# SAMA7G54_DDR3L.net
KiCad netlist of a schematic drawn in Altium Designer
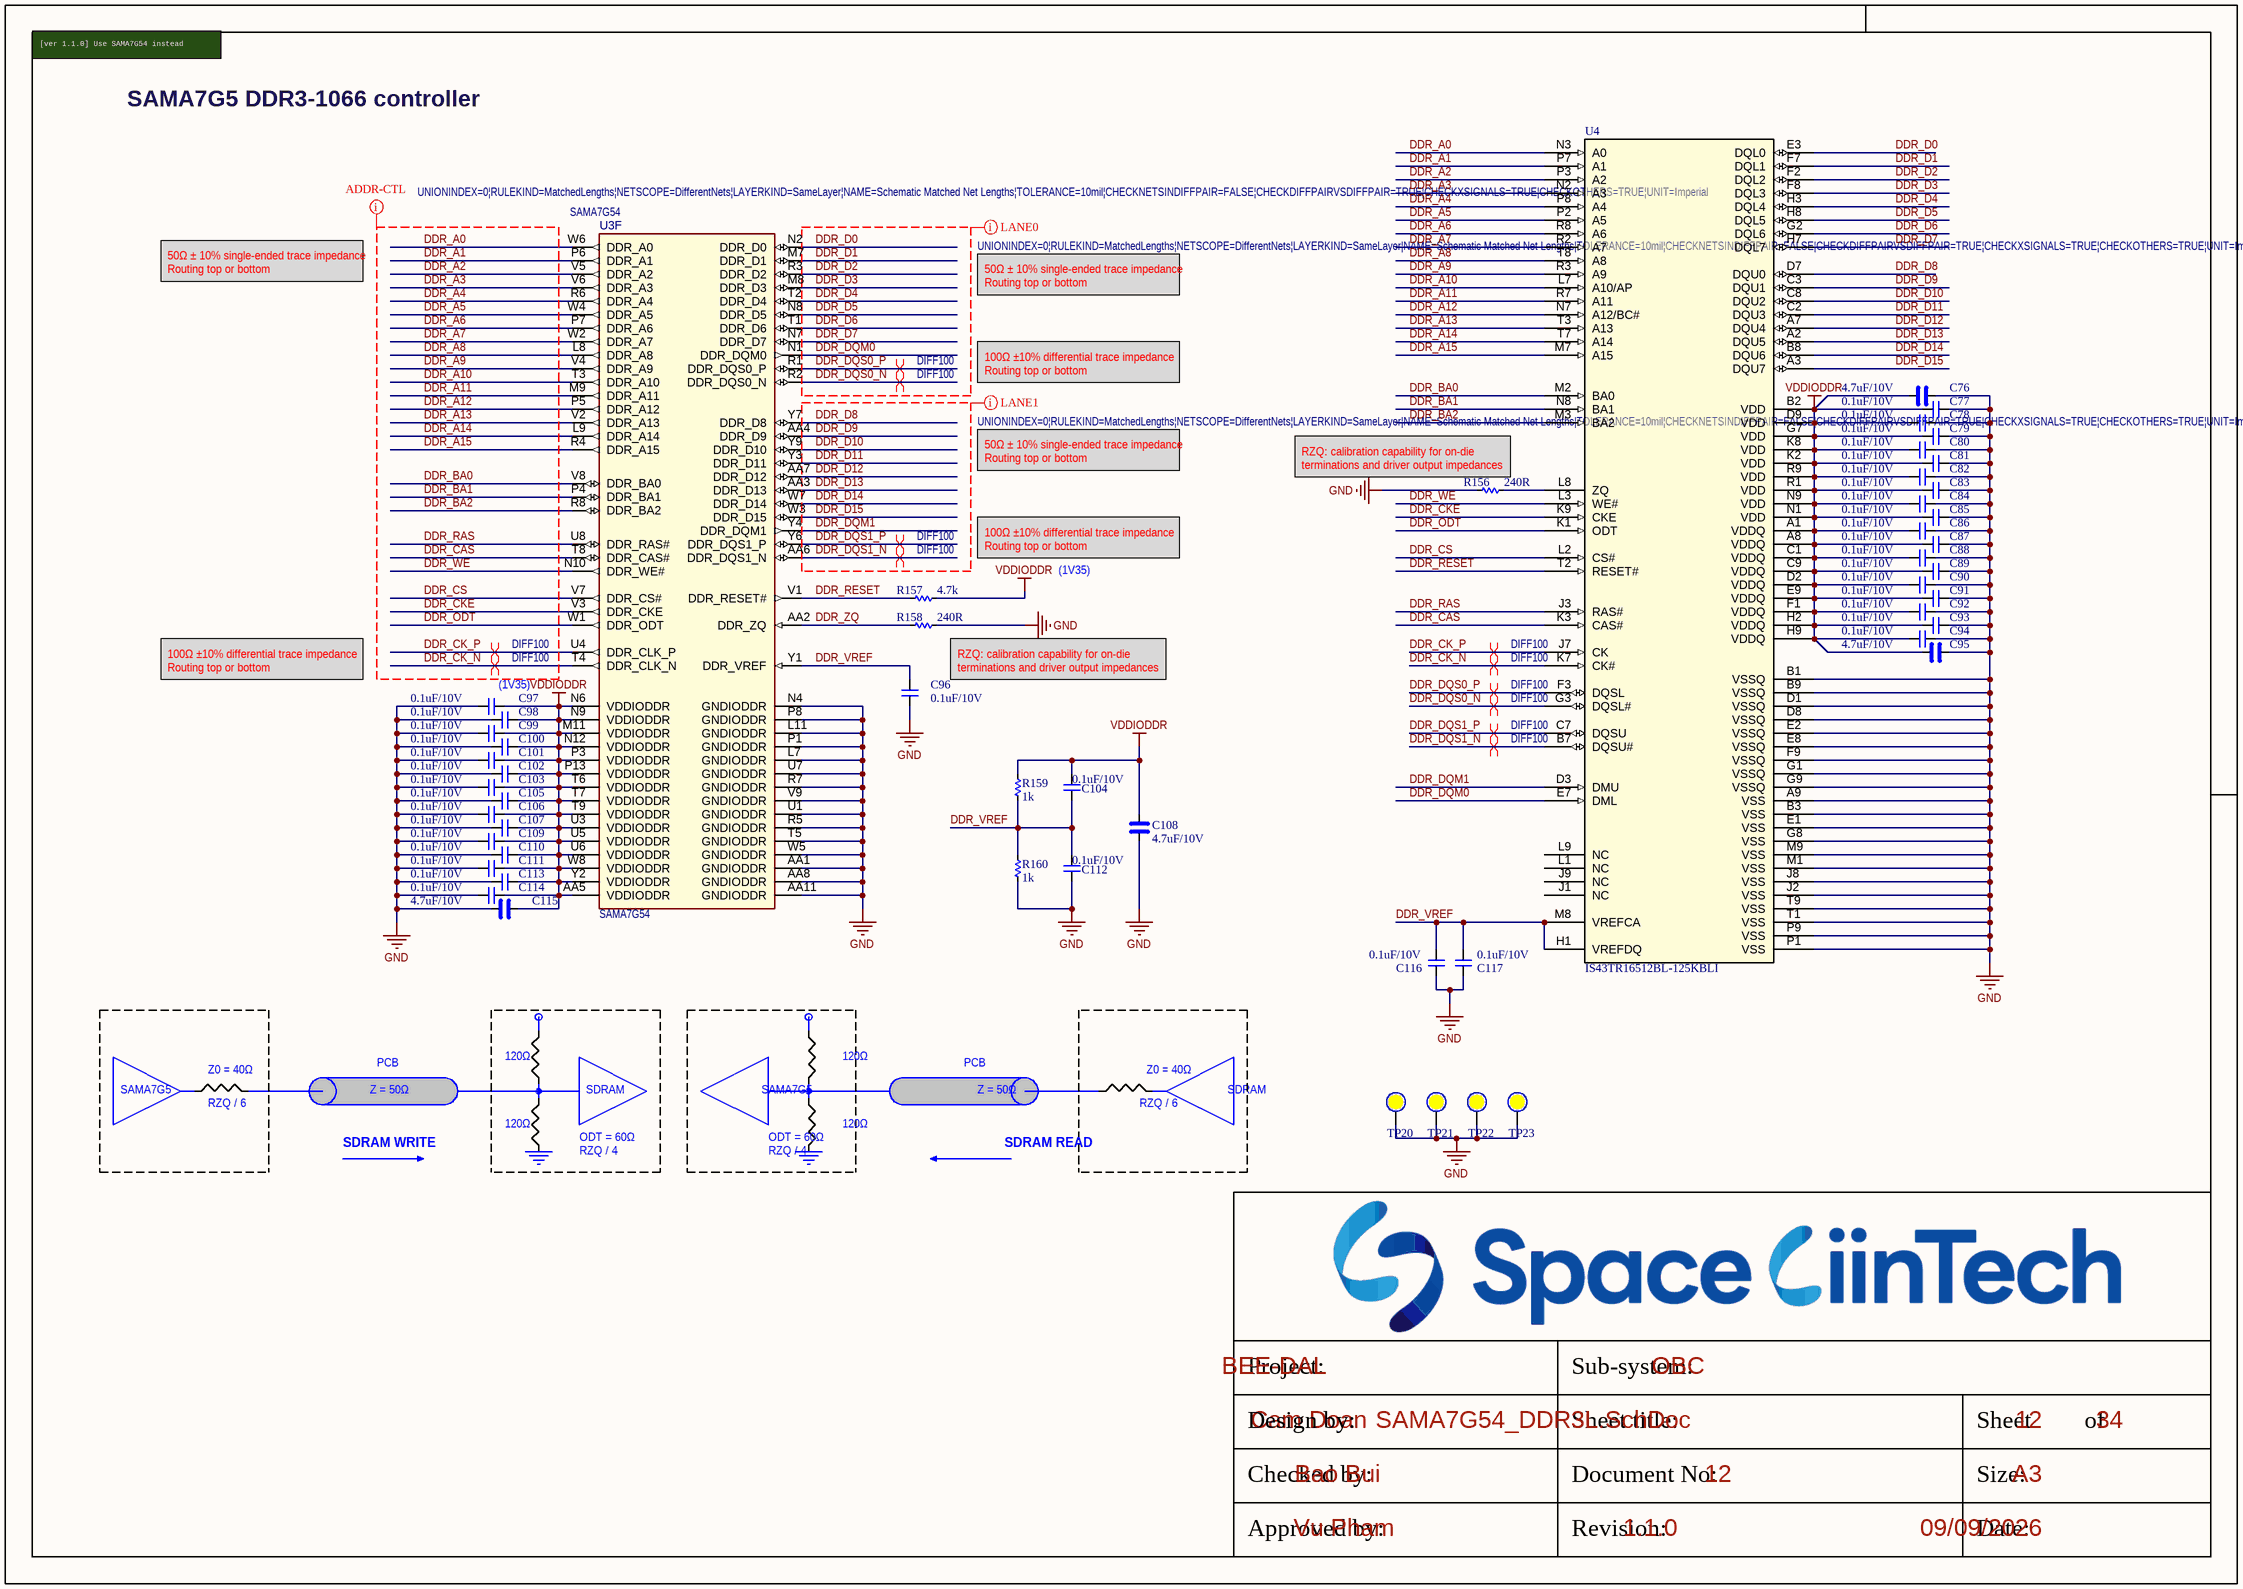
[diagram p0: SAMA7G54_DDR3L.SchDoc]

(export (version "E")
  (design (tool "Eeschema 10.0.6"))
  (components
    (comp (ref "C76")
      (value "4.7uF/10V")
      (footprint "CAP_C_1005X50_L")
      (description "CAP")
      (libsource (lib "LABLIB") (part "_CAP_C_High_2"))
    )
    (comp (ref "C77")
      (value "0.1uF/10V")
      (footprint "CAP_C_0603x30")
      (description "CAP")
      (libsource (lib "LABLIB") (part "_CAP_C_2"))
    )
    (comp (ref "C78")
      (value "0.1uF/10V")
      (footprint "CAP_C_0603x30")
      (description "CAP")
      (libsource (lib "LABLIB") (part "_CAP_C_2"))
    )
    (comp (ref "C79")
      (value "0.1uF/10V")
      (footprint "CAP_C_0603x30")
      (description "CAP")
      (libsource (lib "LABLIB") (part "_CAP_C_2"))
    )
    (comp (ref "C80")
      (value "0.1uF/10V")
      (footprint "CAP_C_0603x30")
      (description "CAP")
      (libsource (lib "LABLIB") (part "_CAP_C_2"))
    )
    (comp (ref "C81")
      (value "0.1uF/10V")
      (footprint "CAP_C_0603x30")
      (description "CAP")
      (libsource (lib "LABLIB") (part "_CAP_C_2"))
    )
    (comp (ref "C82")
      (value "0.1uF/10V")
      (footprint "CAP_C_0603x30")
      (description "CAP")
      (libsource (lib "LABLIB") (part "_CAP_C_2"))
    )
    (comp (ref "C83")
      (value "0.1uF/10V")
      (footprint "CAP_C_0603x30")
      (description "CAP")
      (libsource (lib "LABLIB") (part "_CAP_C_2"))
    )
    (comp (ref "C84")
      (value "0.1uF/10V")
      (footprint "CAP_C_0603x30")
      (description "CAP")
      (libsource (lib "LABLIB") (part "_CAP_C_2"))
    )
    (comp (ref "C85")
      (value "0.1uF/10V")
      (footprint "CAP_C_0603x30")
      (description "CAP")
      (libsource (lib "LABLIB") (part "_CAP_C_2"))
    )
    (comp (ref "C86")
      (value "0.1uF/10V")
      (footprint "CAP_C_0603x30")
      (description "CAP")
      (libsource (lib "LABLIB") (part "_CAP_C_2"))
    )
    (comp (ref "C87")
      (value "0.1uF/10V")
      (footprint "CAP_C_0603x30")
      (description "CAP")
      (libsource (lib "LABLIB") (part "_CAP_C_2"))
    )
    (comp (ref "C88")
      (value "0.1uF/10V")
      (footprint "CAP_C_0603x30")
      (description "CAP")
      (libsource (lib "LABLIB") (part "_CAP_C_2"))
    )
    (comp (ref "C89")
      (value "0.1uF/10V")
      (footprint "CAP_C_0603x30")
      (description "CAP")
      (libsource (lib "LABLIB") (part "_CAP_C_2"))
    )
    (comp (ref "C90")
      (value "0.1uF/10V")
      (footprint "CAP_C_0603x30")
      (description "CAP")
      (libsource (lib "LABLIB") (part "_CAP_C_2"))
    )
    (comp (ref "C91")
      (value "0.1uF/10V")
      (footprint "CAP_C_0603x30")
      (description "CAP")
      (libsource (lib "LABLIB") (part "_CAP_C_2"))
    )
    (comp (ref "C92")
      (value "0.1uF/10V")
      (footprint "CAP_C_0603x30")
      (description "CAP")
      (libsource (lib "LABLIB") (part "_CAP_C_2"))
    )
    (comp (ref "C93")
      (value "0.1uF/10V")
      (footprint "CAP_C_0603x30")
      (description "CAP")
      (libsource (lib "LABLIB") (part "_CAP_C_2"))
    )
    (comp (ref "C94")
      (value "0.1uF/10V")
      (footprint "CAP_C_0603x30")
      (description "CAP")
      (libsource (lib "LABLIB") (part "_CAP_C_2"))
    )
    (comp (ref "C95")
      (value "4.7uF/10V")
      (footprint "CAP_C_1005X50_L")
      (description "CAP")
      (libsource (lib "LABLIB") (part "_CAP_C_High_2"))
    )
    (comp (ref "C96")
      (value "0.1uF/10V")
      (footprint "CAP_C_0603x30")
      (description "CAP")
      (libsource (lib "LABLIB") (part "_CAP_C_2"))
    )
    (comp (ref "C97")
      (value "0.1uF/10V")
      (footprint "CAP_C_0603x30")
      (description "CAP")
      (libsource (lib "LABLIB") (part "_CAP_C_2"))
    )
    (comp (ref "C98")
      (value "0.1uF/10V")
      (footprint "CAP_C_0603x30")
      (description "CAP")
      (libsource (lib "LABLIB") (part "_CAP_C_2"))
    )
    (comp (ref "C99")
      (value "0.1uF/10V")
      (footprint "CAP_C_0603x30")
      (description "CAP")
      (libsource (lib "LABLIB") (part "_CAP_C_2"))
    )
    (comp (ref "C100")
      (value "0.1uF/10V")
      (footprint "CAP_C_0603x30")
      (description "CAP")
      (libsource (lib "LABLIB") (part "_CAP_C_2"))
    )
    (comp (ref "C101")
      (value "0.1uF/10V")
      (footprint "CAP_C_0603x30")
      (description "CAP")
      (libsource (lib "LABLIB") (part "_CAP_C_2"))
    )
    (comp (ref "C102")
      (value "0.1uF/10V")
      (footprint "CAP_C_0603x30")
      (description "CAP")
      (libsource (lib "LABLIB") (part "_CAP_C_2"))
    )
    (comp (ref "C103")
      (value "0.1uF/10V")
      (footprint "CAP_C_0603x30")
      (description "CAP")
      (libsource (lib "LABLIB") (part "_CAP_C_2"))
    )
    (comp (ref "C104")
      (value "0.1uF/10V")
      (footprint "CAP_C_0603x30")
      (description "CAP")
      (libsource (lib "LABLIB") (part "_CAP_C_2"))
    )
    (comp (ref "C105")
      (value "0.1uF/10V")
      (footprint "CAP_C_0603x30")
      (description "CAP")
      (libsource (lib "LABLIB") (part "_CAP_C_2"))
    )
    (comp (ref "C106")
      (value "0.1uF/10V")
      (footprint "CAP_C_0603x30")
      (description "CAP")
      (libsource (lib "LABLIB") (part "_CAP_C_2"))
    )
    (comp (ref "C107")
      (value "0.1uF/10V")
      (footprint "CAP_C_0603x30")
      (description "CAP")
      (libsource (lib "LABLIB") (part "_CAP_C_2"))
    )
    (comp (ref "C108")
      (value "4.7uF/10V")
      (footprint "CAP_C_1005X50_L")
      (description "CAP")
      (libsource (lib "LABLIB") (part "_CAP_C_High_2"))
    )
    (comp (ref "C109")
      (value "0.1uF/10V")
      (footprint "CAP_C_0603x30")
      (description "CAP")
      (libsource (lib "LABLIB") (part "_CAP_C_2"))
    )
    (comp (ref "C110")
      (value "0.1uF/10V")
      (footprint "CAP_C_0603x30")
      (description "CAP")
      (libsource (lib "LABLIB") (part "_CAP_C_2"))
    )
    (comp (ref "C111")
      (value "0.1uF/10V")
      (footprint "CAP_C_0603x30")
      (description "CAP")
      (libsource (lib "LABLIB") (part "_CAP_C_2"))
    )
    (comp (ref "C112")
      (value "0.1uF/10V")
      (footprint "CAP_C_0603x30")
      (description "CAP")
      (libsource (lib "LABLIB") (part "_CAP_C_2"))
    )
    (comp (ref "C113")
      (value "0.1uF/10V")
      (footprint "CAP_C_0603x30")
      (description "CAP")
      (libsource (lib "LABLIB") (part "_CAP_C_2"))
    )
    (comp (ref "C114")
      (value "0.1uF/10V")
      (footprint "CAP_C_0603x30")
      (description "CAP")
      (libsource (lib "LABLIB") (part "_CAP_C_2"))
    )
    (comp (ref "C115")
      (value "4.7uF/10V")
      (footprint "CAP_C_1005X50_L")
      (description "CAP")
      (libsource (lib "LABLIB") (part "_CAP_C_High_2"))
    )
    (comp (ref "C116")
      (value "0.1uF/10V")
      (footprint "CAP_C_0603x30")
      (description "CAP")
      (libsource (lib "LABLIB") (part "_CAP_C_2"))
    )
    (comp (ref "C117")
      (value "0.1uF/10V")
      (footprint "CAP_C_0603x30")
      (description "CAP")
      (libsource (lib "LABLIB") (part "_CAP_C_2"))
    )
    (comp (ref "R156")
      (value "240R")
      (footprint "RES_C_0603X30")
      (description "RES")
      (libsource (lib "LABLIB") (part "_RES_B_2"))
    )
    (comp (ref "R157")
      (value "4.7k")
      (footprint "RES_C_1005x30_L")
      (description "RES")
      (libsource (lib "LABLIB") (part "_RES_B_2"))
    )
    (comp (ref "R158")
      (value "240R")
      (footprint "RES_C_0603X30")
      (description "RES")
      (libsource (lib "LABLIB") (part "_RES_B_2"))
    )
    (comp (ref "R159")
      (value "1k")
      (footprint "RES_C_1005x30_L")
      (description "RES")
      (libsource (lib "LABLIB") (part "_RES_B_2"))
    )
    (comp (ref "R160")
      (value "1k")
      (footprint "RES_C_1005x30_L")
      (description "RES")
      (libsource (lib "LABLIB") (part "_RES_B_2"))
    )
    (comp (ref "TP20")
      (value "~")
      (footprint "Testpoint_80_pin0")
      (description "Test Point")
      (libsource (lib "IFBschelib") (part "Test Point"))
    )
    (comp (ref "TP21")
      (value "~")
      (footprint "Testpoint_80_pin0")
      (description "Test Point")
      (libsource (lib "IFBschelib") (part "Test Point"))
    )
    (comp (ref "TP22")
      (value "~")
      (footprint "Testpoint_80_pin0")
      (description "Test Point")
      (libsource (lib "IFBschelib") (part "Test Point"))
    )
    (comp (ref "TP23")
      (value "~")
      (footprint "Testpoint_80_pin0")
      (description "Test Point")
      (libsource (lib "IFBschelib") (part "Test Point"))
    )
    (comp (ref "U3")
      (value "SAMA7G54")
      (footprint "TFBGA-343_14x14 - 2.5mm")
      (description "SAMA7G54 MPU 1000MHz Cortex-A7 TFBGA-343")
      (fields (field (name "ALTIUM_VALUE") "SAMA7G54") (field (name "OWNER") "Ciprian Abramov"))
      (libsource (lib "LABLIB") (part "SAMA7G54"))
    )
    (comp (ref "U4")
      (value "IS43TR16512BL-125KBLI")
      (footprint "TWBGA96_ISI")
      (description "DDR3L")
      (fields (field (name "COPYRIGHT") "Copyright (C) 2025 Ultra Librarian. All rights reserved."))
      (libsource (lib "LABLIB") (part "IC_RAM_IS43TR16512BL-125KBLI"))
    )
  )
  (nets
    (net (code "1") (name "/DDR_A0") (class "Default")
      (node (ref "U3") (pin "W6") (pinfunction "DDR_A0_W6") (pintype "output"))
      (node (ref "U4") (pin "N3") (pinfunction "A0_N3") (pintype "input"))
    )
    (net (code "2") (name "/DDR_A1") (class "Default")
      (node (ref "U3") (pin "P6") (pinfunction "DDR_A1_P6") (pintype "output"))
      (node (ref "U4") (pin "P7") (pinfunction "A1_P7") (pintype "input"))
    )
    (net (code "3") (name "/DDR_A2") (class "Default")
      (node (ref "U3") (pin "V5") (pinfunction "DDR_A2_V5") (pintype "output"))
      (node (ref "U4") (pin "P3") (pinfunction "A2_P3") (pintype "input"))
    )
    (net (code "4") (name "/DDR_A3") (class "Default")
      (node (ref "U3") (pin "V6") (pinfunction "DDR_A3_V6") (pintype "output"))
      (node (ref "U4") (pin "N2") (pinfunction "A3_N2") (pintype "input"))
    )
    (net (code "5") (name "/DDR_A4") (class "Default")
      (node (ref "U3") (pin "R6") (pinfunction "DDR_A4_R6") (pintype "output"))
      (node (ref "U4") (pin "P8") (pinfunction "A4_P8") (pintype "input"))
    )
    (net (code "6") (name "/DDR_A5") (class "Default")
      (node (ref "U3") (pin "W4") (pinfunction "DDR_A5_W4") (pintype "output"))
      (node (ref "U4") (pin "P2") (pinfunction "A5_P2") (pintype "input"))
    )
    (net (code "7") (name "/DDR_A6") (class "Default")
      (node (ref "U3") (pin "P7") (pinfunction "DDR_A6_P7") (pintype "output"))
      (node (ref "U4") (pin "R8") (pinfunction "A6_R8") (pintype "input"))
    )
    (net (code "8") (name "/DDR_A7") (class "Default")
      (node (ref "U3") (pin "W2") (pinfunction "DDR_A7_W2") (pintype "output"))
      (node (ref "U4") (pin "R2") (pinfunction "A7_R2") (pintype "input"))
    )
    (net (code "9") (name "/DDR_A8") (class "Default")
      (node (ref "U3") (pin "L8") (pinfunction "DDR_A8_L8") (pintype "output"))
      (node (ref "U4") (pin "T8") (pinfunction "A8_T8") (pintype "input"))
    )
    (net (code "10") (name "/DDR_A9") (class "Default")
      (node (ref "U3") (pin "V4") (pinfunction "DDR_A9_V4") (pintype "output"))
      (node (ref "U4") (pin "R3") (pinfunction "A9_R3") (pintype "input"))
    )
    (net (code "11") (name "/DDR_A10") (class "Default")
      (node (ref "U3") (pin "T3") (pinfunction "DDR_A10_T3") (pintype "output"))
      (node (ref "U4") (pin "L7") (pinfunction "A10/AP_L7") (pintype "input"))
    )
    (net (code "12") (name "/DDR_A11") (class "Default")
      (node (ref "U3") (pin "M9") (pinfunction "DDR_A11_M9") (pintype "output"))
      (node (ref "U4") (pin "R7") (pinfunction "A11_R7") (pintype "input"))
    )
    (net (code "13") (name "/DDR_A12") (class "Default")
      (node (ref "U3") (pin "P5") (pinfunction "DDR_A12_P5") (pintype "output"))
      (node (ref "U4") (pin "N7") (pinfunction "A12/BC#_N7") (pintype "input"))
    )
    (net (code "14") (name "/DDR_A13") (class "Default")
      (node (ref "U3") (pin "V2") (pinfunction "DDR_A13_V2") (pintype "output"))
      (node (ref "U4") (pin "T3") (pinfunction "A13_T3") (pintype "input"))
    )
    (net (code "15") (name "/DDR_A14") (class "Default")
      (node (ref "U3") (pin "L9") (pinfunction "DDR_A14_L9") (pintype "output"))
      (node (ref "U4") (pin "T7") (pinfunction "A14_T7") (pintype "input"))
    )
    (net (code "16") (name "/DDR_A15") (class "Default")
      (node (ref "U3") (pin "R4") (pinfunction "DDR_A15_R4") (pintype "output"))
      (node (ref "U4") (pin "M7") (pinfunction "A15_M7") (pintype "input"))
    )
    (net (code "17") (name "/DDR_BA0") (class "Default")
      (node (ref "U3") (pin "V8") (pinfunction "DDR_BA0_V8") (pintype "bidirectional"))
      (node (ref "U4") (pin "M2") (pinfunction "BA0_M2") (pintype "input"))
    )
    (net (code "18") (name "/DDR_BA1") (class "Default")
      (node (ref "U3") (pin "P4") (pinfunction "DDR_BA1_P4") (pintype "bidirectional"))
      (node (ref "U4") (pin "N8") (pinfunction "BA1_N8") (pintype "input"))
    )
    (net (code "19") (name "/DDR_BA2") (class "Default")
      (node (ref "U3") (pin "R8") (pinfunction "DDR_BA2_R8") (pintype "bidirectional"))
      (node (ref "U4") (pin "M3") (pinfunction "BA2_M3") (pintype "input"))
    )
    (net (code "20") (name "/DDR_CAS") (class "Default")
      (node (ref "U3") (pin "T8") (pinfunction "DDR_CAS#_T8") (pintype "bidirectional"))
      (node (ref "U4") (pin "K3") (pinfunction "CAS#_K3") (pintype "input"))
    )
    (net (code "21") (name "/DDR_CKE") (class "Default")
      (node (ref "U3") (pin "V3") (pinfunction "DDR_CKE_V3") (pintype "output"))
      (node (ref "U4") (pin "K9") (pinfunction "CKE_K9") (pintype "input"))
    )
    (net (code "22") (name "/DDR_CK_N") (class "Default")
      (node (ref "U3") (pin "T4") (pinfunction "DDR_CLK_N_T4") (pintype "output"))
      (node (ref "U4") (pin "K7") (pinfunction "CK#_K7") (pintype "input"))
    )
    (net (code "23") (name "/DDR_CK_P") (class "Default")
      (node (ref "U3") (pin "U4") (pinfunction "DDR_CLK_P_U4") (pintype "output"))
      (node (ref "U4") (pin "J7") (pinfunction "CK_J7") (pintype "input"))
    )
    (net (code "24") (name "/DDR_CS") (class "Default")
      (node (ref "U3") (pin "V7") (pinfunction "DDR_CS#_V7") (pintype "output"))
      (node (ref "U4") (pin "L2") (pinfunction "CS#_L2") (pintype "input"))
    )
    (net (code "25") (name "/DDR_D0") (class "Default")
      (node (ref "U3") (pin "N2") (pinfunction "DDR_D0_N2") (pintype "bidirectional"))
      (node (ref "U4") (pin "E3") (pinfunction "DQL0_E3") (pintype "bidirectional"))
    )
    (net (code "26") (name "/DDR_D1") (class "Default")
      (node (ref "U3") (pin "M7") (pinfunction "DDR_D1_M7") (pintype "bidirectional"))
      (node (ref "U4") (pin "F7") (pinfunction "DQL1_F7") (pintype "bidirectional"))
    )
    (net (code "27") (name "/DDR_D2") (class "Default")
      (node (ref "U3") (pin "R3") (pinfunction "DDR_D2_R3") (pintype "bidirectional"))
      (node (ref "U4") (pin "F2") (pinfunction "DQL2_F2") (pintype "bidirectional"))
    )
    (net (code "28") (name "/DDR_D3") (class "Default")
      (node (ref "U3") (pin "M8") (pinfunction "DDR_D3_M8") (pintype "bidirectional"))
      (node (ref "U4") (pin "F8") (pinfunction "DQL3_F8") (pintype "bidirectional"))
    )
    (net (code "29") (name "/DDR_D4") (class "Default")
      (node (ref "U3") (pin "T2") (pinfunction "DDR_D4_T2") (pintype "bidirectional"))
      (node (ref "U4") (pin "H3") (pinfunction "DQL4_H3") (pintype "bidirectional"))
    )
    (net (code "30") (name "/DDR_D5") (class "Default")
      (node (ref "U3") (pin "N8") (pinfunction "DDR_D5_N8") (pintype "bidirectional"))
      (node (ref "U4") (pin "H8") (pinfunction "DQL5_H8") (pintype "bidirectional"))
    )
    (net (code "31") (name "/DDR_D6") (class "Default")
      (node (ref "U3") (pin "T1") (pinfunction "DDR_D6_T1") (pintype "bidirectional"))
      (node (ref "U4") (pin "G2") (pinfunction "DQL6_G2") (pintype "bidirectional"))
    )
    (net (code "32") (name "/DDR_D7") (class "Default")
      (node (ref "U3") (pin "N7") (pinfunction "DDR_D7_N7") (pintype "bidirectional"))
      (node (ref "U4") (pin "H7") (pinfunction "DQL7_H7") (pintype "bidirectional"))
    )
    (net (code "33") (name "/DDR_D8") (class "Default")
      (node (ref "U3") (pin "Y7") (pinfunction "DDR_D8_Y7") (pintype "bidirectional"))
      (node (ref "U4") (pin "D7") (pinfunction "DQU0_D7") (pintype "bidirectional"))
    )
    (net (code "34") (name "/DDR_D9") (class "Default")
      (node (ref "U3") (pin "AA4") (pinfunction "DDR_D9_AA4") (pintype "bidirectional"))
      (node (ref "U4") (pin "C3") (pinfunction "DQU1_C3") (pintype "bidirectional"))
    )
    (net (code "35") (name "/DDR_D10") (class "Default")
      (node (ref "U3") (pin "Y9") (pinfunction "DDR_D10_Y9") (pintype "bidirectional"))
      (node (ref "U4") (pin "C8") (pinfunction "DQU2_C8") (pintype "bidirectional"))
    )
    (net (code "36") (name "/DDR_D11") (class "Default")
      (node (ref "U3") (pin "Y3") (pinfunction "DDR_D11_Y3") (pintype "bidirectional"))
      (node (ref "U4") (pin "C2") (pinfunction "DQU3_C2") (pintype "bidirectional"))
    )
    (net (code "37") (name "/DDR_D12") (class "Default")
      (node (ref "U3") (pin "AA7") (pinfunction "DDR_D12_AA7") (pintype "bidirectional"))
      (node (ref "U4") (pin "A7") (pinfunction "DQU4_A7") (pintype "bidirectional"))
    )
    (net (code "38") (name "/DDR_D13") (class "Default")
      (node (ref "U3") (pin "AA3") (pinfunction "DDR_D13_AA3") (pintype "bidirectional"))
      (node (ref "U4") (pin "A2") (pinfunction "DQU5_A2") (pintype "bidirectional"))
    )
    (net (code "39") (name "/DDR_D14") (class "Default")
      (node (ref "U3") (pin "W7") (pinfunction "DDR_D14_W7") (pintype "bidirectional"))
      (node (ref "U4") (pin "B8") (pinfunction "DQU6_B8") (pintype "bidirectional"))
    )
    (net (code "40") (name "/DDR_D15") (class "Default")
      (node (ref "U3") (pin "W3") (pinfunction "DDR_D15_W3") (pintype "bidirectional"))
      (node (ref "U4") (pin "A3") (pinfunction "DQU7_A3") (pintype "bidirectional"))
    )
    (net (code "41") (name "/DDR_DQM0") (class "Default")
      (node (ref "U3") (pin "N1") (pinfunction "DDR_DQM0_N1") (pintype "output"))
      (node (ref "U4") (pin "E7") (pinfunction "DML_E7") (pintype "input"))
    )
    (net (code "42") (name "/DDR_DQM1") (class "Default")
      (node (ref "U3") (pin "Y4") (pinfunction "DDR_DQM1_Y4") (pintype "output"))
      (node (ref "U4") (pin "D3") (pinfunction "DMU_D3") (pintype "input"))
    )
    (net (code "43") (name "/DDR_DQS0_N") (class "Default")
      (node (ref "U3") (pin "R2") (pinfunction "DDR_DQS0_N_R2") (pintype "bidirectional"))
      (node (ref "U4") (pin "G3") (pinfunction "DQSL#_G3") (pintype "bidirectional"))
    )
    (net (code "44") (name "/DDR_DQS0_P") (class "Default")
      (node (ref "U3") (pin "R1") (pinfunction "DDR_DQS0_P_R1") (pintype "bidirectional"))
      (node (ref "U4") (pin "F3") (pinfunction "DQSL_F3") (pintype "bidirectional"))
    )
    (net (code "45") (name "/DDR_DQS1_N") (class "Default")
      (node (ref "U3") (pin "AA6") (pinfunction "DDR_DQS1_N_AA6") (pintype "bidirectional"))
      (node (ref "U4") (pin "B7") (pinfunction "DQSU#_B7") (pintype "bidirectional"))
    )
    (net (code "46") (name "/DDR_DQS1_P") (class "Default")
      (node (ref "U3") (pin "Y6") (pinfunction "DDR_DQS1_P_Y6") (pintype "bidirectional"))
      (node (ref "U4") (pin "C7") (pinfunction "DQSU_C7") (pintype "bidirectional"))
    )
    (net (code "47") (name "/DDR_ODT") (class "Default")
      (node (ref "U3") (pin "W1") (pinfunction "DDR_ODT_W1") (pintype "output"))
      (node (ref "U4") (pin "K1") (pinfunction "ODT_K1") (pintype "input"))
    )
    (net (code "48") (name "/DDR_RAS") (class "Default")
      (node (ref "U3") (pin "U8") (pinfunction "DDR_RAS#_U8") (pintype "bidirectional"))
      (node (ref "U4") (pin "J3") (pinfunction "RAS#_J3") (pintype "input"))
    )
    (net (code "49") (name "/DDR_RESET") (class "Default")
      (node (ref "R157") (pin "2") (pinfunction "2_2") (pintype "passive"))
      (node (ref "U3") (pin "V1") (pinfunction "DDR_RESET#_V1") (pintype "output"))
      (node (ref "U4") (pin "T2") (pinfunction "RESET#_T2") (pintype "input"))
    )
    (net (code "50") (name "/DDR_VREF") (class "Default")
      (node (ref "C104") (pin "2") (pinfunction "2_2") (pintype "passive"))
      (node (ref "C112") (pin "1") (pinfunction "1_1") (pintype "passive"))
      (node (ref "C116") (pin "1") (pinfunction "1_1") (pintype "passive"))
      (node (ref "C117") (pin "1") (pinfunction "1_1") (pintype "passive"))
      (node (ref "C96") (pin "1") (pinfunction "1_1") (pintype "passive"))
      (node (ref "R159") (pin "2") (pinfunction "2_2") (pintype "passive"))
      (node (ref "R160") (pin "1") (pinfunction "1_1") (pintype "passive"))
      (node (ref "U3") (pin "Y1") (pinfunction "DDR_VREF_Y1") (pintype "input"))
      (node (ref "U4") (pin "H1") (pinfunction "VREFDQ_H1") (pintype "power_in"))
      (node (ref "U4") (pin "M8") (pinfunction "VREFCA_M8") (pintype "power_in"))
    )
    (net (code "51") (name "/DDR_WE") (class "Default")
      (node (ref "U3") (pin "N10") (pinfunction "DDR_WE#_N10") (pintype "output"))
      (node (ref "U4") (pin "L3") (pinfunction "WE#_L3") (pintype "input"))
    )
    (net (code "52") (name "/DDR_ZQ") (class "Default")
      (node (ref "R158") (pin "2") (pinfunction "2_2") (pintype "passive"))
      (node (ref "U3") (pin "AA2") (pinfunction "DDR_ZQ_AA2") (pintype "input"))
    )
    (net (code "53") (name "GND") (class "Default")
      (node (ref "C100") (pin "2") (pinfunction "2_2") (pintype "passive"))
      (node (ref "C101") (pin "2") (pinfunction "2_2") (pintype "passive"))
      (node (ref "C102") (pin "2") (pinfunction "2_2") (pintype "passive"))
      (node (ref "C103") (pin "2") (pinfunction "2_2") (pintype "passive"))
      (node (ref "C105") (pin "2") (pinfunction "2_2") (pintype "passive"))
      (node (ref "C106") (pin "2") (pinfunction "2_2") (pintype "passive"))
      (node (ref "C107") (pin "2") (pinfunction "2_2") (pintype "passive"))
      (node (ref "C108") (pin "2") (pinfunction "2_2") (pintype "passive"))
      (node (ref "C109") (pin "2") (pinfunction "2_2") (pintype "passive"))
      (node (ref "C110") (pin "2") (pinfunction "2_2") (pintype "passive"))
      (node (ref "C111") (pin "2") (pinfunction "2_2") (pintype "passive"))
      (node (ref "C112") (pin "2") (pinfunction "2_2") (pintype "passive"))
      (node (ref "C113") (pin "2") (pinfunction "2_2") (pintype "passive"))
      (node (ref "C114") (pin "2") (pinfunction "2_2") (pintype "passive"))
      (node (ref "C115") (pin "2") (pinfunction "2_2") (pintype "passive"))
      (node (ref "C116") (pin "2") (pinfunction "2_2") (pintype "passive"))
      (node (ref "C117") (pin "2") (pinfunction "2_2") (pintype "passive"))
      (node (ref "C76") (pin "1") (pinfunction "1_1") (pintype "passive"))
      (node (ref "C77") (pin "1") (pinfunction "1_1") (pintype "passive"))
      (node (ref "C78") (pin "1") (pinfunction "1_1") (pintype "passive"))
      (node (ref "C79") (pin "1") (pinfunction "1_1") (pintype "passive"))
      (node (ref "C80") (pin "1") (pinfunction "1_1") (pintype "passive"))
      (node (ref "C81") (pin "1") (pinfunction "1_1") (pintype "passive"))
      (node (ref "C82") (pin "1") (pinfunction "1_1") (pintype "passive"))
      (node (ref "C83") (pin "1") (pinfunction "1_1") (pintype "passive"))
      (node (ref "C84") (pin "1") (pinfunction "1_1") (pintype "passive"))
      (node (ref "C85") (pin "1") (pinfunction "1_1") (pintype "passive"))
      (node (ref "C86") (pin "1") (pinfunction "1_1") (pintype "passive"))
      (node (ref "C87") (pin "1") (pinfunction "1_1") (pintype "passive"))
      (node (ref "C88") (pin "1") (pinfunction "1_1") (pintype "passive"))
      (node (ref "C89") (pin "1") (pinfunction "1_1") (pintype "passive"))
      (node (ref "C90") (pin "1") (pinfunction "1_1") (pintype "passive"))
      (node (ref "C91") (pin "1") (pinfunction "1_1") (pintype "passive"))
      (node (ref "C92") (pin "1") (pinfunction "1_1") (pintype "passive"))
      (node (ref "C93") (pin "1") (pinfunction "1_1") (pintype "passive"))
      (node (ref "C94") (pin "1") (pinfunction "1_1") (pintype "passive"))
      (node (ref "C95") (pin "1") (pinfunction "1_1") (pintype "passive"))
      (node (ref "C96") (pin "2") (pinfunction "2_2") (pintype "passive"))
      (node (ref "C97") (pin "2") (pinfunction "2_2") (pintype "passive"))
      (node (ref "C98") (pin "2") (pinfunction "2_2") (pintype "passive"))
      (node (ref "C99") (pin "2") (pinfunction "2_2") (pintype "passive"))
      (node (ref "R156") (pin "2") (pinfunction "2_2") (pintype "passive"))
      (node (ref "R158") (pin "1") (pinfunction "1_1") (pintype "passive"))
      (node (ref "R160") (pin "2") (pinfunction "2_2") (pintype "passive"))
      (node (ref "TP20") (pin "0") (pinfunction "0_0") (pintype "passive"))
      (node (ref "TP21") (pin "0") (pinfunction "0_0") (pintype "passive"))
      (node (ref "TP22") (pin "0") (pinfunction "0_0") (pintype "passive"))
      (node (ref "TP23") (pin "0") (pinfunction "0_0") (pintype "passive"))
      (node (ref "U3") (pin "AA1") (pinfunction "GNDIODDR_AA1") (pintype "power_in"))
      (node (ref "U3") (pin "AA11") (pinfunction "GNDIODDR_AA11") (pintype "power_in"))
      (node (ref "U3") (pin "AA8") (pinfunction "GNDIODDR_AA8") (pintype "power_in"))
      (node (ref "U3") (pin "L11") (pinfunction "GNDIODDR_L11") (pintype "power_in"))
      (node (ref "U3") (pin "L7") (pinfunction "GNDIODDR_L7") (pintype "power_in"))
      (node (ref "U3") (pin "N4") (pinfunction "GNDIODDR_N4") (pintype "power_in"))
      (node (ref "U3") (pin "P1") (pinfunction "GNDIODDR_P1") (pintype "power_in"))
      (node (ref "U3") (pin "P8") (pinfunction "GNDIODDR_P8") (pintype "power_in"))
      (node (ref "U3") (pin "R5") (pinfunction "GNDIODDR_R5") (pintype "power_in"))
      (node (ref "U3") (pin "R7") (pinfunction "GNDIODDR_R7") (pintype "power_in"))
      (node (ref "U3") (pin "T5") (pinfunction "GNDIODDR_T5") (pintype "power_in"))
      (node (ref "U3") (pin "U1") (pinfunction "GNDIODDR_U1") (pintype "power_in"))
      (node (ref "U3") (pin "U7") (pinfunction "GNDIODDR_U7") (pintype "power_in"))
      (node (ref "U3") (pin "V9") (pinfunction "GNDIODDR_V9") (pintype "power_in"))
      (node (ref "U3") (pin "W5") (pinfunction "GNDIODDR_W5") (pintype "power_in"))
      (node (ref "U4") (pin "A9") (pinfunction "VSS_A9") (pintype "power_in"))
      (node (ref "U4") (pin "B1") (pinfunction "VSSQ_B1") (pintype "power_in"))
      (node (ref "U4") (pin "B3") (pinfunction "VSS_B3") (pintype "power_in"))
      (node (ref "U4") (pin "B9") (pinfunction "VSSQ_B9") (pintype "power_in"))
      (node (ref "U4") (pin "D1") (pinfunction "VSSQ_D1") (pintype "power_in"))
      (node (ref "U4") (pin "D8") (pinfunction "VSSQ_D8") (pintype "power_in"))
      (node (ref "U4") (pin "E1") (pinfunction "VSS_E1") (pintype "power_in"))
      (node (ref "U4") (pin "E2") (pinfunction "VSSQ_E2") (pintype "power_in"))
      (node (ref "U4") (pin "E8") (pinfunction "VSSQ_E8") (pintype "power_in"))
      (node (ref "U4") (pin "F9") (pinfunction "VSSQ_F9") (pintype "power_in"))
      (node (ref "U4") (pin "G1") (pinfunction "VSSQ_G1") (pintype "power_in"))
      (node (ref "U4") (pin "G8") (pinfunction "VSS_G8") (pintype "power_in"))
      (node (ref "U4") (pin "G9") (pinfunction "VSSQ_G9") (pintype "power_in"))
      (node (ref "U4") (pin "J2") (pinfunction "VSS_J2") (pintype "power_in"))
      (node (ref "U4") (pin "J8") (pinfunction "VSS_J8") (pintype "power_in"))
      (node (ref "U4") (pin "M1") (pinfunction "VSS_M1") (pintype "power_in"))
      (node (ref "U4") (pin "M9") (pinfunction "VSS_M9") (pintype "power_in"))
      (node (ref "U4") (pin "P1") (pinfunction "VSS_P1") (pintype "power_in"))
      (node (ref "U4") (pin "P9") (pinfunction "VSS_P9") (pintype "power_in"))
      (node (ref "U4") (pin "T1") (pinfunction "VSS_T1") (pintype "power_in"))
      (node (ref "U4") (pin "T9") (pinfunction "VSS_T9") (pintype "power_in"))
    )
    (net (code "54") (name "Net-(U4-ZQ)") (class "Default")
      (node (ref "R156") (pin "1") (pinfunction "1_1") (pintype "passive"))
      (node (ref "U4") (pin "L8") (pinfunction "ZQ_L8") (pintype "power_in"))
    )
    (net (code "55") (name "VDDIODDR") (class "Default")
      (node (ref "C100") (pin "1") (pinfunction "1_1") (pintype "passive"))
      (node (ref "C101") (pin "1") (pinfunction "1_1") (pintype "passive"))
      (node (ref "C102") (pin "1") (pinfunction "1_1") (pintype "passive"))
      (node (ref "C103") (pin "1") (pinfunction "1_1") (pintype "passive"))
      (node (ref "C104") (pin "1") (pinfunction "1_1") (pintype "passive"))
      (node (ref "C105") (pin "1") (pinfunction "1_1") (pintype "passive"))
      (node (ref "C106") (pin "1") (pinfunction "1_1") (pintype "passive"))
      (node (ref "C107") (pin "1") (pinfunction "1_1") (pintype "passive"))
      (node (ref "C108") (pin "1") (pinfunction "1_1") (pintype "passive"))
      (node (ref "C109") (pin "1") (pinfunction "1_1") (pintype "passive"))
      (node (ref "C110") (pin "1") (pinfunction "1_1") (pintype "passive"))
      (node (ref "C111") (pin "1") (pinfunction "1_1") (pintype "passive"))
      (node (ref "C113") (pin "1") (pinfunction "1_1") (pintype "passive"))
      (node (ref "C114") (pin "1") (pinfunction "1_1") (pintype "passive"))
      (node (ref "C115") (pin "1") (pinfunction "1_1") (pintype "passive"))
      (node (ref "C76") (pin "2") (pinfunction "2_2") (pintype "passive"))
      (node (ref "C77") (pin "2") (pinfunction "2_2") (pintype "passive"))
      (node (ref "C78") (pin "2") (pinfunction "2_2") (pintype "passive"))
      (node (ref "C79") (pin "2") (pinfunction "2_2") (pintype "passive"))
      (node (ref "C80") (pin "2") (pinfunction "2_2") (pintype "passive"))
      (node (ref "C81") (pin "2") (pinfunction "2_2") (pintype "passive"))
      (node (ref "C82") (pin "2") (pinfunction "2_2") (pintype "passive"))
      (node (ref "C83") (pin "2") (pinfunction "2_2") (pintype "passive"))
      (node (ref "C84") (pin "2") (pinfunction "2_2") (pintype "passive"))
      (node (ref "C85") (pin "2") (pinfunction "2_2") (pintype "passive"))
      (node (ref "C86") (pin "2") (pinfunction "2_2") (pintype "passive"))
      (node (ref "C87") (pin "2") (pinfunction "2_2") (pintype "passive"))
      (node (ref "C88") (pin "2") (pinfunction "2_2") (pintype "passive"))
      (node (ref "C89") (pin "2") (pinfunction "2_2") (pintype "passive"))
      (node (ref "C90") (pin "2") (pinfunction "2_2") (pintype "passive"))
      (node (ref "C91") (pin "2") (pinfunction "2_2") (pintype "passive"))
      (node (ref "C92") (pin "2") (pinfunction "2_2") (pintype "passive"))
      (node (ref "C93") (pin "2") (pinfunction "2_2") (pintype "passive"))
      (node (ref "C94") (pin "2") (pinfunction "2_2") (pintype "passive"))
      (node (ref "C95") (pin "2") (pinfunction "2_2") (pintype "passive"))
      (node (ref "C97") (pin "1") (pinfunction "1_1") (pintype "passive"))
      (node (ref "C98") (pin "1") (pinfunction "1_1") (pintype "passive"))
      (node (ref "C99") (pin "1") (pinfunction "1_1") (pintype "passive"))
      (node (ref "R157") (pin "1") (pinfunction "1_1") (pintype "passive"))
      (node (ref "R159") (pin "1") (pinfunction "1_1") (pintype "passive"))
      (node (ref "U3") (pin "AA5") (pinfunction "VDDIODDR_AA5") (pintype "power_in"))
      (node (ref "U3") (pin "M11") (pinfunction "VDDIODDR_M11") (pintype "power_in"))
      (node (ref "U3") (pin "N12") (pinfunction "VDDIODDR_N12") (pintype "power_in"))
      (node (ref "U3") (pin "N6") (pinfunction "VDDIODDR_N6") (pintype "power_in"))
      (node (ref "U3") (pin "N9") (pinfunction "VDDIODDR_N9") (pintype "power_in"))
      (node (ref "U3") (pin "P13") (pinfunction "VDDIODDR_P13") (pintype "power_in"))
      (node (ref "U3") (pin "P3") (pinfunction "VDDIODDR_P3") (pintype "power_in"))
      (node (ref "U3") (pin "T6") (pinfunction "VDDIODDR_T6") (pintype "power_in"))
      (node (ref "U3") (pin "T7") (pinfunction "VDDIODDR_T7") (pintype "power_in"))
      (node (ref "U3") (pin "T9") (pinfunction "VDDIODDR_T9") (pintype "power_in"))
      (node (ref "U3") (pin "U3") (pinfunction "VDDIODDR_U3") (pintype "power_in"))
      (node (ref "U3") (pin "U5") (pinfunction "VDDIODDR_U5") (pintype "power_in"))
      (node (ref "U3") (pin "U6") (pinfunction "VDDIODDR_U6") (pintype "power_in"))
      (node (ref "U3") (pin "W8") (pinfunction "VDDIODDR_W8") (pintype "power_in"))
      (node (ref "U3") (pin "Y2") (pinfunction "VDDIODDR_Y2") (pintype "power_in"))
      (node (ref "U4") (pin "A1") (pinfunction "VDDQ_A1") (pintype "power_in"))
      (node (ref "U4") (pin "A8") (pinfunction "VDDQ_A8") (pintype "power_in"))
      (node (ref "U4") (pin "B2") (pinfunction "VDD_B2") (pintype "power_in"))
      (node (ref "U4") (pin "C1") (pinfunction "VDDQ_C1") (pintype "power_in"))
      (node (ref "U4") (pin "C9") (pinfunction "VDDQ_C9") (pintype "power_in"))
      (node (ref "U4") (pin "D2") (pinfunction "VDDQ_D2") (pintype "power_in"))
      (node (ref "U4") (pin "D9") (pinfunction "VDD_D9") (pintype "power_in"))
      (node (ref "U4") (pin "E9") (pinfunction "VDDQ_E9") (pintype "power_in"))
      (node (ref "U4") (pin "F1") (pinfunction "VDDQ_F1") (pintype "power_in"))
      (node (ref "U4") (pin "G7") (pinfunction "VDD_G7") (pintype "power_in"))
      (node (ref "U4") (pin "H2") (pinfunction "VDDQ_H2") (pintype "power_in"))
      (node (ref "U4") (pin "H9") (pinfunction "VDDQ_H9") (pintype "power_in"))
      (node (ref "U4") (pin "K2") (pinfunction "VDD_K2") (pintype "power_in"))
      (node (ref "U4") (pin "K8") (pinfunction "VDD_K8") (pintype "power_in"))
      (node (ref "U4") (pin "N1") (pinfunction "VDD_N1") (pintype "power_in"))
      (node (ref "U4") (pin "N9") (pinfunction "VDD_N9") (pintype "power_in"))
      (node (ref "U4") (pin "R1") (pinfunction "VDD_R1") (pintype "power_in"))
      (node (ref "U4") (pin "R9") (pinfunction "VDD_R9") (pintype "power_in"))
    )
    (net (code "56") (name "unconnected-(U4-NC-PadJ1)") (class "Default")
      (node (ref "U4") (pin "J1") (pinfunction "NC_J1") (pintype "passive"))
    )
    (net (code "57") (name "unconnected-(U4-NC-PadJ9)") (class "Default")
      (node (ref "U4") (pin "J9") (pinfunction "NC_J9") (pintype "passive"))
    )
    (net (code "58") (name "unconnected-(U4-NC-PadL1)") (class "Default")
      (node (ref "U4") (pin "L1") (pinfunction "NC_L1") (pintype "passive"))
    )
    (net (code "59") (name "unconnected-(U4-NC-PadL9)") (class "Default")
      (node (ref "U4") (pin "L9") (pinfunction "NC_L9") (pintype "passive"))
    )
  )
)
